# uShake_POWER.net
KiCad netlist of a schematic drawn in Altium Designer
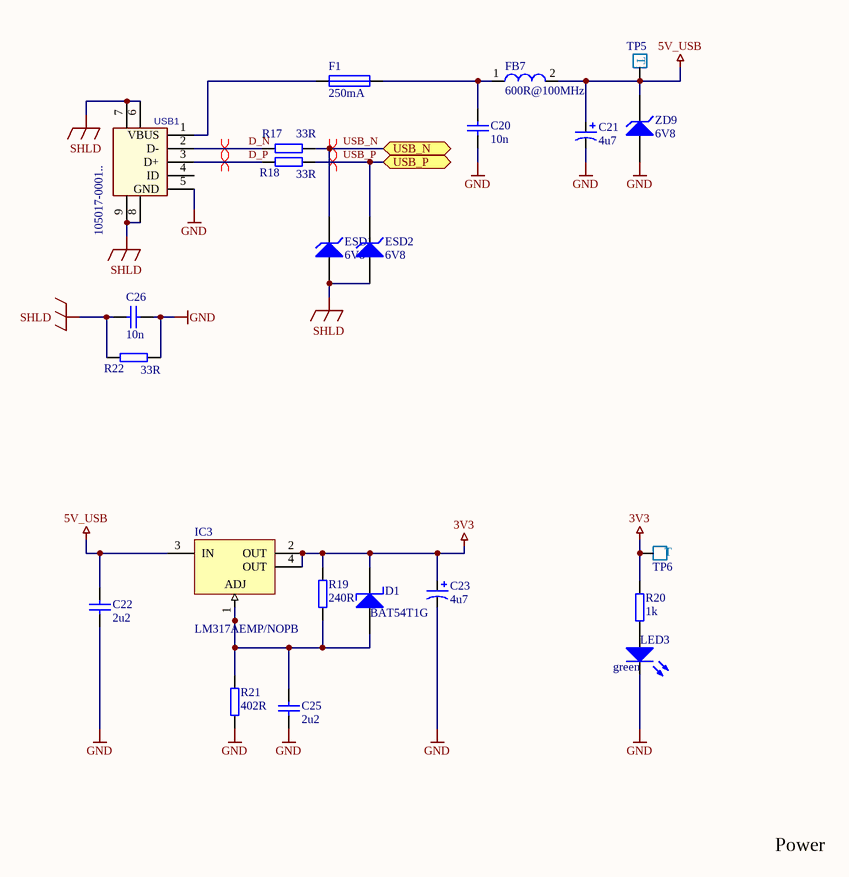
[diagram p0: uShake_POWER.SchDoc]

(export (version "E")
  (design (tool "Eeschema 10.0.6"))
  (components
    (comp (ref "C20")
      (value "10n")
      (footprint "SMD_C0603")
      (description "Capacitor")
      (libsource (lib "WatchDogAlarm_rev1_3") (part "CAP"))
    )
    (comp (ref "C21")
      (value "4u7")
      (footprint "Tantalum 3216")
      (description "Generic polarized capacitor")
      (libsource (lib "WatchDogAlarm_rev1_3") (part "Capacitor - polarized"))
    )
    (comp (ref "C22")
      (value "2u2")
      (footprint "SMD_C0805")
      (description "Capacitor")
      (libsource (lib "WatchDogAlarm_rev1_3") (part "CAP"))
    )
    (comp (ref "C23")
      (value "4u7")
      (footprint "Tantalum 3216")
      (description "Generic polarized capacitor")
      (libsource (lib "WatchDogAlarm_rev1_3") (part "Capacitor - polarized"))
    )
    (comp (ref "C25")
      (value "2u2")
      (footprint "SMD_C0805")
      (description "Capacitor")
      (libsource (lib "WatchDogAlarm_rev1_3") (part "CAP"))
    )
    (comp (ref "C26")
      (value "10n")
      (footprint "SMD_C0603")
      (description "Capacitor")
      (libsource (lib "WatchDogAlarm_rev1_3") (part "CAP"))
    )
    (comp (ref "D1")
      (value "BAT54T1G")
      (footprint "SOD-123")
      (fields (field (name "MANUFACTURER") "ON SEMICONDUCTOR"))
      (libsource (lib "WatchDogAlarm_rev1_3") (part "DIODE_SCHOTTKY"))
    )
    (comp (ref "ESD1")
      (value "6V8")
      (footprint "SMD_R0603")
      (description "ESD Protection device")
      (fields (field (name "MANUFACTURER") "ON Semiconductor") (field (name "PARTNUMBER") "BZX84C6V8LT1G"))
      (libsource (lib "WatchDogAlarm_rev1_3") (part "ZenerDiode"))
    )
    (comp (ref "ESD2")
      (value "6V8")
      (footprint "SMD_R0603")
      (description "ESD Protection device")
      (fields (field (name "MANUFACTURER") "ON Semiconductor") (field (name "PARTNUMBER") "BZX84C6V8LT1G"))
      (libsource (lib "WatchDogAlarm_rev1_3") (part "ZenerDiode"))
    )
    (comp (ref "F1")
      (value "250mA")
      (footprint "PPTCF 1206")
      (description "Resettable Fuse, PPTC, 1206 (3216 Metric), POLYFUSE 1206L Series, 16 VDC, 250 mA, 500 mA, 0.08 s")
      (fields (field (name "MANUFACTURER") "Littelfuse"))
      (libsource (lib "WatchDogAlarm_rev1_3") (part "PolyFuse"))
    )
    (comp (ref "FB7")
      (value "600R@100MHz")
      (footprint "SMD_R0603")
      (description "Ferrite bead")
      (libsource (lib "WatchDogAlarm_rev1_3") (part "FB"))
    )
    (comp (ref "IC3")
      (value "LM317AEMP/NOPB")
      (footprint "WatchDogAlarm_rev1_3:SOT-223")
      (description "3-Terminal Adjustable Regulator")
      (fields (field (name "MANUFACTURER") "TEXAS INSTRUMENTS"))
      (libsource (lib "WatchDogAlarm_rev1_3") (part "LM317KC"))
    )
    (comp (ref "LED3") (value "green") (footprint "SMD_LD0603") (libsource (lib "Atlan") (part "LED")))
    (comp (ref "R17")
      (value "33R")
      (footprint "SMD_R0603")
      (libsource (lib "WatchDogAlarm_rev1_3") (part "RESISTOR"))
    )
    (comp (ref "R18")
      (value "33R")
      (footprint "SMD_R0603")
      (libsource (lib "WatchDogAlarm_rev1_3") (part "RESISTOR"))
    )
    (comp (ref "R19")
      (value "240R")
      (footprint "SMD_R0603")
      (libsource (lib "WatchDogAlarm_rev1_3") (part "RESISTOR"))
    )
    (comp (ref "R20")
      (value "1k")
      (footprint "SMD_R0603")
      (libsource (lib "WatchDogAlarm_rev1_3") (part "RESISTOR"))
    )
    (comp (ref "R21")
      (value "402R")
      (footprint "SMD_R0603")
      (libsource (lib "WatchDogAlarm_rev1_3") (part "RESISTOR"))
    )
    (comp (ref "R22")
      (value "33R")
      (footprint "SMD_R0603")
      (libsource (lib "WatchDogAlarm_rev1_3") (part "RESISTOR"))
    )
    (comp (ref "TP5")
      (value "TEST_PAD_1.5mm")
      (footprint "TEST_PAD_1.5mm")
      (libsource (lib "Atlan") (part "TEST_PAD"))
    )
    (comp (ref "TP6")
      (value "TEST_PAD_1.5mm")
      (footprint "TEST_PAD_1.5mm")
      (libsource (lib "Atlan") (part "TEST_PAD"))
    )
    (comp (ref "USB1")
      (value "105017-0001..")
      (footprint "USB_MICRO_B")
      (fields (field (name "MANUFACTURER") "MOLEX"))
      (libsource (lib "unidisp43_r1.0") (part "Micro_USB_MIUSB-F5M-BB-U"))
    )
    (comp (ref "ZD9")
      (value "6V8")
      (footprint "SOT-23")
      (description "Zener Diode")
      (fields (field (name "MANUFACTURER") "ON Semiconductor") (field (name "PARTNUMBER") "BZX84C6V8LT1G"))
      (libsource (lib "WatchDogAlarm_rev1_3") (part "ZenerDiode"))
    )
  )
  (nets
    (net (code "1") (name "/D_N") (class "Default")
      (node (ref "R17") (pin "2") (pintype "passive"))
      (node (ref "USB1") (pin "2") (pinfunction "D-_2") (pintype "passive"))
    )
    (net (code "2") (name "/D_P") (class "Default")
      (node (ref "R18") (pin "2") (pintype "passive"))
      (node (ref "USB1") (pin "3") (pinfunction "D+_3") (pintype "passive"))
    )
    (net (code "3") (name "/USB_N") (class "Default")
      (node (ref "ESD1") (pin "3") (pinfunction "K_3") (pintype "passive"))
      (node (ref "R17") (pin "1") (pintype "passive"))
    )
    (net (code "4") (name "/USB_P") (class "Default")
      (node (ref "ESD2") (pin "3") (pinfunction "K_3") (pintype "passive"))
      (node (ref "R18") (pin "1") (pintype "passive"))
    )
    (net (code "5") (name "3V3") (class "Default")
      (node (ref "C23") (pin "1") (pinfunction "1_1") (pintype "passive"))
      (node (ref "D1") (pin "1") (pinfunction "K_1") (pintype "passive"))
      (node (ref "IC3") (pin "2") (pinfunction "OUT_2") (pintype "power_in"))
      (node (ref "IC3") (pin "4") (pinfunction "OUT_4") (pintype "power_in"))
      (node (ref "R19") (pin "2") (pintype "passive"))
      (node (ref "R20") (pin "2") (pintype "passive"))
      (node (ref "TP6") (pin "1") (pintype "passive"))
    )
    (net (code "6") (name "5V_USB") (class "Default")
      (node (ref "C21") (pin "1") (pinfunction "1_1") (pintype "passive"))
      (node (ref "C22") (pin "2") (pinfunction "2_2") (pintype "passive"))
      (node (ref "FB7") (pin "2") (pinfunction "2_2") (pintype "passive"))
      (node (ref "IC3") (pin "3") (pinfunction "IN_3") (pintype "power_in"))
      (node (ref "TP5") (pin "1") (pintype "passive"))
      (node (ref "ZD9") (pin "3") (pinfunction "K_3") (pintype "passive"))
    )
    (net (code "7") (name "GND") (class "Default")
      (node (ref "C20") (pin "1") (pinfunction "1_1") (pintype "passive"))
      (node (ref "C21") (pin "2") (pinfunction "2_2") (pintype "passive"))
      (node (ref "C22") (pin "1") (pinfunction "1_1") (pintype "passive"))
      (node (ref "C23") (pin "2") (pinfunction "2_2") (pintype "passive"))
      (node (ref "C25") (pin "1") (pinfunction "1_1") (pintype "passive"))
      (node (ref "C26") (pin "1") (pinfunction "1_1") (pintype "passive"))
      (node (ref "LED3") (pin "1") (pinfunction "K_1") (pintype "passive"))
      (node (ref "R21") (pin "1") (pintype "passive"))
      (node (ref "R22") (pin "1") (pintype "passive"))
      (node (ref "USB1") (pin "5") (pinfunction "GND_5") (pintype "power_in"))
      (node (ref "ZD9") (pin "1") (pinfunction "A_1") (pintype "passive"))
    )
    (net (code "8") (name "Net-(C20-Pad2)") (class "Default")
      (node (ref "C20") (pin "2") (pinfunction "2_2") (pintype "passive"))
      (node (ref "F1") (pin "2") (pinfunction "2_2") (pintype "passive"))
      (node (ref "FB7") (pin "1") (pinfunction "1_1") (pintype "passive"))
    )
    (net (code "9") (name "Net-(D1-A)") (class "Default")
      (node (ref "C25") (pin "2") (pinfunction "2_2") (pintype "passive"))
      (node (ref "D1") (pin "2") (pinfunction "A_2") (pintype "passive"))
      (node (ref "IC3") (pin "1") (pinfunction "ADJ_1") (pintype "input"))
      (node (ref "R19") (pin "1") (pintype "passive"))
      (node (ref "R21") (pin "2") (pintype "passive"))
    )
    (net (code "10") (name "Net-(LED3-A)") (class "Default")
      (node (ref "LED3") (pin "2") (pinfunction "A_2") (pintype "passive"))
      (node (ref "R20") (pin "1") (pintype "passive"))
    )
    (net (code "11") (name "Net-(USB1-VBUS)") (class "Default")
      (node (ref "F1") (pin "1") (pinfunction "1_1") (pintype "passive"))
      (node (ref "USB1") (pin "1") (pinfunction "VBUS_1") (pintype "power_in"))
    )
    (net (code "12") (name "SHLD") (class "Default")
      (node (ref "C26") (pin "2") (pinfunction "2_2") (pintype "passive"))
      (node (ref "ESD1") (pin "1") (pinfunction "A_1") (pintype "passive"))
      (node (ref "ESD2") (pin "1") (pinfunction "A_1") (pintype "passive"))
      (node (ref "R22") (pin "2") (pintype "passive"))
      (node (ref "USB1") (pin "6") (pinfunction "GND1_6") (pintype "passive"))
      (node (ref "USB1") (pin "7") (pinfunction "GND2_7") (pintype "passive"))
      (node (ref "USB1") (pin "8") (pinfunction "GND2_8") (pintype "passive"))
      (node (ref "USB1") (pin "9") (pinfunction "GND3_9") (pintype "passive"))
    )
    (net (code "13") (name "unconnected-(USB1-ID-Pad4)") (class "Default")
      (node (ref "USB1") (pin "4") (pinfunction "ID_4") (pintype "passive"))
    )
  )
)
